# teensyflash.net
KiCad netlist of a schematic drawn in EAGLE
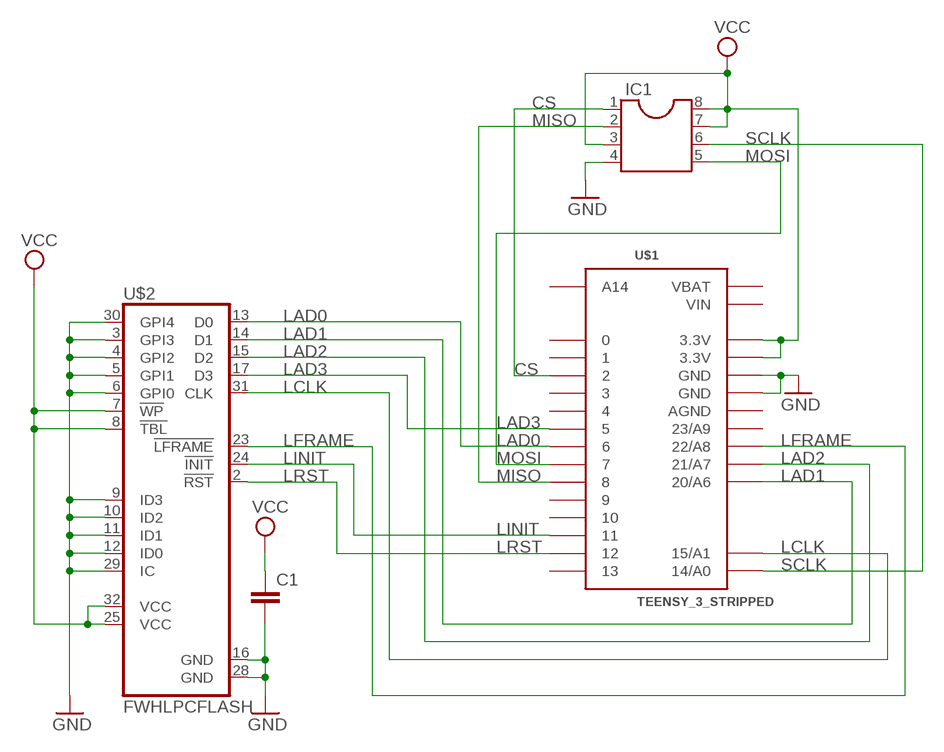
[diagram p0: schematic, sheet 1]

(export (version "E")
  (design (tool "Eeschema 10.0.6"))
  (components
    (comp (ref "C1")
      (value "C-EUC0805")
      (footprint "eagle-import:C0805")
      (libsource (lib "eagle-import") (part "C-EUC0805"))
    )
    (comp (ref "IC1")
      (value "DIL8")
      (footprint "eagle-import:DIL08")
      (libsource (lib "eagle-import") (part "DIL8"))
    )
    (comp (ref "U$1")
      (value "TEENSY_3_STRIPPED")
      (footprint "eagle-import:TEENSY_3_STRIPPED")
      (libsource (lib "eagle-import") (part "TEENSY_3_STRIPPED"))
    )
    (comp (ref "U$2")
      (value "FWHLPCFLASH")
      (footprint "eagle-import:PLCC32")
      (libsource (lib "eagle-import") (part "FWHLPCFLASH"))
    )
  )
  (nets
    (net (code "1") (name "/AGND") (class "Default")
      (node (ref "U$1") (pin "AGND") (pinfunction "AGND_AGND") (pintype "power_in"))
    )
    (net (code "2") (name "/CS") (class "Default")
      (node (ref "IC1") (pin "1") (pinfunction "1_1") (pintype "passive"))
      (node (ref "U$1") (pin "2") (pinfunction "2_2") (pintype "bidirectional"))
    )
    (net (code "3") (name "/LAD0") (class "Default")
      (node (ref "U$1") (pin "6") (pinfunction "6_6") (pintype "bidirectional"))
      (node (ref "U$2") (pin "13") (pinfunction "D0_13") (pintype "bidirectional"))
    )
    (net (code "4") (name "/LAD1") (class "Default")
      (node (ref "U$1") (pin "20/A6") (pinfunction "20/A6_20/A6") (pintype "bidirectional"))
      (node (ref "U$2") (pin "14") (pinfunction "D1_14") (pintype "bidirectional"))
    )
    (net (code "5") (name "/LAD2") (class "Default")
      (node (ref "U$1") (pin "21/A7") (pinfunction "21/A7_21/A7") (pintype "bidirectional"))
      (node (ref "U$2") (pin "15") (pinfunction "D2_15") (pintype "bidirectional"))
    )
    (net (code "6") (name "/LAD3") (class "Default")
      (node (ref "U$1") (pin "5") (pinfunction "5_5") (pintype "bidirectional"))
      (node (ref "U$2") (pin "17") (pinfunction "D3_17") (pintype "bidirectional"))
    )
    (net (code "7") (name "/LCLK") (class "Default")
      (node (ref "U$1") (pin "15/A1") (pinfunction "15/A1_15/A1") (pintype "bidirectional"))
      (node (ref "U$2") (pin "31") (pinfunction "CLK_31") (pintype "input"))
    )
    (net (code "8") (name "/LFRAME") (class "Default")
      (node (ref "U$1") (pin "22/A8") (pinfunction "22/A8_22/A8") (pintype "bidirectional"))
      (node (ref "U$2") (pin "23") (pinfunction "~{LFRAME}_23") (pintype "input"))
    )
    (net (code "9") (name "/LINIT") (class "Default")
      (node (ref "U$1") (pin "11") (pinfunction "11_11") (pintype "bidirectional"))
      (node (ref "U$2") (pin "24") (pinfunction "~{INIT}_24") (pintype "input"))
    )
    (net (code "10") (name "/LRST") (class "Default")
      (node (ref "U$1") (pin "12") (pinfunction "12_12") (pintype "bidirectional"))
      (node (ref "U$2") (pin "2") (pinfunction "~{RST}_2") (pintype "input"))
    )
    (net (code "11") (name "/MISO") (class "Default")
      (node (ref "IC1") (pin "2") (pinfunction "2_2") (pintype "passive"))
      (node (ref "U$1") (pin "8") (pinfunction "8_8") (pintype "bidirectional"))
    )
    (net (code "12") (name "/MOSI") (class "Default")
      (node (ref "IC1") (pin "5") (pinfunction "5_5") (pintype "passive"))
      (node (ref "U$1") (pin "7") (pinfunction "7_7") (pintype "bidirectional"))
    )
    (net (code "13") (name "/SCLK") (class "Default")
      (node (ref "IC1") (pin "6") (pinfunction "6_6") (pintype "passive"))
      (node (ref "U$1") (pin "14/A0") (pinfunction "14/A0_14/A0") (pintype "bidirectional"))
    )
    (net (code "14") (name "/VBAT") (class "Default")
      (node (ref "U$1") (pin "VBAT") (pinfunction "VBAT_VBAT") (pintype "power_in"))
    )
    (net (code "15") (name "/VIN") (class "Default")
      (node (ref "U$1") (pin "VIN") (pinfunction "VIN_VIN") (pintype "power_in"))
    )
    (net (code "16") (name "GND") (class "Default")
      (node (ref "C1") (pin "2") (pinfunction "2_2") (pintype "passive"))
      (node (ref "IC1") (pin "4") (pinfunction "4_4") (pintype "passive"))
      (node (ref "U$1") (pin "GND") (pinfunction "GND_GND") (pintype "power_in"))
      (node (ref "U$1") (pin "GND1") (pinfunction "GND_GND1") (pintype "power_in"))
      (node (ref "U$2") (pin "10") (pinfunction "ID2_10") (pintype "input"))
      (node (ref "U$2") (pin "11") (pinfunction "ID1_11") (pintype "input"))
      (node (ref "U$2") (pin "12") (pinfunction "ID0_12") (pintype "input"))
      (node (ref "U$2") (pin "16") (pinfunction "GND_16") (pintype "power_in"))
      (node (ref "U$2") (pin "28") (pinfunction "GND_28") (pintype "power_in"))
      (node (ref "U$2") (pin "29") (pinfunction "IC_29") (pintype "input"))
      (node (ref "U$2") (pin "3") (pinfunction "GPI3_3") (pintype "input"))
      (node (ref "U$2") (pin "30") (pinfunction "GPI4_30") (pintype "input"))
      (node (ref "U$2") (pin "4") (pinfunction "GPI2_4") (pintype "input"))
      (node (ref "U$2") (pin "5") (pinfunction "GPI1_5") (pintype "input"))
      (node (ref "U$2") (pin "6") (pinfunction "GPI0_6") (pintype "input"))
      (node (ref "U$2") (pin "9") (pinfunction "ID3_9") (pintype "input"))
    )
    (net (code "17") (name "VCC") (class "Default")
      (node (ref "C1") (pin "1") (pinfunction "1_1") (pintype "passive"))
      (node (ref "IC1") (pin "3") (pinfunction "3_3") (pintype "passive"))
      (node (ref "IC1") (pin "7") (pinfunction "7_7") (pintype "passive"))
      (node (ref "IC1") (pin "8") (pinfunction "8_8") (pintype "passive"))
      (node (ref "U$1") (pin "3.3V") (pinfunction "3.3V_3.3V") (pintype "power_in"))
      (node (ref "U$1") (pin "3.3V1") (pinfunction "3.3V_3.3V1") (pintype "power_in"))
      (node (ref "U$2") (pin "25") (pinfunction "VCC_25") (pintype "power_in"))
      (node (ref "U$2") (pin "32") (pinfunction "VCC_32") (pintype "power_in"))
      (node (ref "U$2") (pin "7") (pinfunction "~{WP}_7") (pintype "input"))
      (node (ref "U$2") (pin "8") (pinfunction "~{TBL}_8") (pintype "input"))
    )
    (net (code "18") (name "unconnected-(U$1-A14-PadRESET)") (class "Default")
      (node (ref "U$1") (pin "RESET") (pinfunction "A14_RESET") (pintype "bidirectional"))
    )
    (net (code "19") (name "unconnected-(U$1-Pad0)") (class "Default")
      (node (ref "U$1") (pin "0") (pinfunction "0_0") (pintype "bidirectional"))
    )
    (net (code "20") (name "unconnected-(U$1-Pad1)") (class "Default")
      (node (ref "U$1") (pin "1") (pinfunction "1_1") (pintype "bidirectional"))
    )
    (net (code "21") (name "unconnected-(U$1-Pad3)") (class "Default")
      (node (ref "U$1") (pin "3") (pinfunction "3_3") (pintype "bidirectional"))
    )
    (net (code "22") (name "unconnected-(U$1-Pad4)") (class "Default")
      (node (ref "U$1") (pin "4") (pinfunction "4_4") (pintype "bidirectional"))
    )
    (net (code "23") (name "unconnected-(U$1-Pad9)") (class "Default")
      (node (ref "U$1") (pin "9") (pinfunction "9_9") (pintype "bidirectional"))
    )
    (net (code "24") (name "unconnected-(U$1-Pad10)") (class "Default")
      (node (ref "U$1") (pin "10") (pinfunction "10_10") (pintype "bidirectional"))
    )
    (net (code "25") (name "unconnected-(U$1-Pad13)") (class "Default")
      (node (ref "U$1") (pin "13") (pinfunction "13_13") (pintype "bidirectional"))
    )
    (net (code "26") (name "unconnected-(U$1-Pad23{slash}A9)") (class "Default")
      (node (ref "U$1") (pin "23/A9") (pinfunction "23/A9_23/A9") (pintype "bidirectional"))
    )
  )
)
